# watchdog.net
KiCad netlist of a schematic drawn in Altium Designer
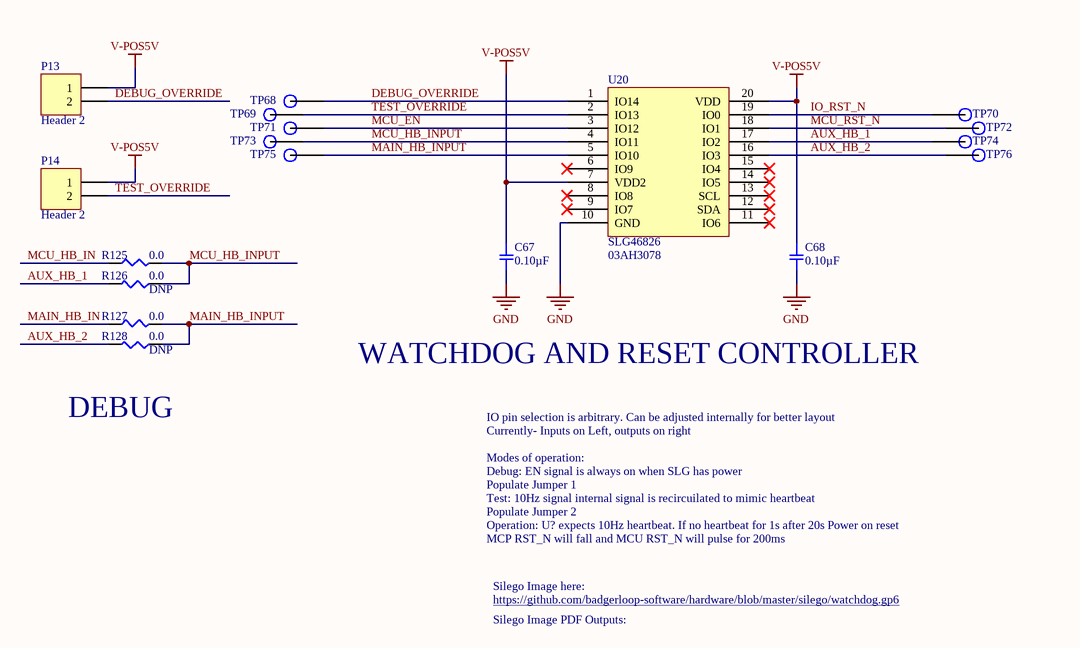
[diagram p0: watchdog.SchDoc]

(export (version "E")
  (design (tool "Eeschema 10.0.6"))
  (components
    (comp (ref "C67")
      (value "0.10µF")
      (footprint "SMD-0805C")
      (description "CAP CER 0.1UF 25V X7R 0805")
      (fields
        (field (name "DIGI-KEY PART NUMBER") "490-12754-1-ND")
        (field (name "PART NUMBER") "GRM219R71E104KA01D")
      )
      (libsource (lib "capacitors") (part "GRM219R71E104KA01D"))
    )
    (comp (ref "C68")
      (value "0.10µF")
      (footprint "SMD-0805C")
      (description "CAP CER 0.1UF 25V X7R 0805")
      (fields
        (field (name "DIGI-KEY PART NUMBER") "490-12754-1-ND")
        (field (name "PART NUMBER") "GRM219R71E104KA01D")
      )
      (libsource (lib "capacitors") (part "GRM219R71E104KA01D"))
    )
    (comp (ref "P13")
      (value "Header 2")
      (footprint "Pin Header 1x2 TH Pitch 2.54mm")
      (description "Header, 2-Pin")
      (fields (field (name "PUBLISHER") "Altium Limited"))
      (libsource (lib "connector") (part "Header 2"))
    )
    (comp (ref "P14")
      (value "Header 2")
      (footprint "Pin Header 1x2 TH Pitch 2.54mm")
      (description "Header, 2-Pin")
      (fields (field (name "PUBLISHER") "Altium Limited"))
      (libsource (lib "connector") (part "Header 2"))
    )
    (comp (ref "R125")
      (value "0.0")
      (footprint "SMD-0805-RES")
      (description "RES SMD 0.0 OHM JUMPER 1/8W 0805")
      (fields (field (name "PART NUMBER") "ERJ-6GEY0R00V") (field (name "DIGI-KEY PART NUMBER") "P0.0ACT-ND"))
      (libsource (lib "resistors") (part "ERJ-6GEY0R00V"))
    )
    (comp (ref "R126")
      (value "0.0")
      (footprint "SMD-0805-RES")
      (description "RES SMD 0.0 OHM JUMPER 1/8W 0805")
      (fields
        (field (name "PART NUMBER") "ERJ-6GEY0R00V")
        (field (name "DIGI-KEY PART NUMBER") "P0.0ACT-ND")
        (field (name "DNP") "DNP")
      )
      (libsource (lib "resistors") (part "ERJ-6GEY0R00V"))
    )
    (comp (ref "R127")
      (value "0.0")
      (footprint "SMD-0805-RES")
      (description "RES SMD 0.0 OHM JUMPER 1/8W 0805")
      (fields (field (name "PART NUMBER") "ERJ-6GEY0R00V") (field (name "DIGI-KEY PART NUMBER") "P0.0ACT-ND"))
      (libsource (lib "resistors") (part "ERJ-6GEY0R00V"))
    )
    (comp (ref "R128")
      (value "0.0")
      (footprint "SMD-0805-RES")
      (description "RES SMD 0.0 OHM JUMPER 1/8W 0805")
      (fields
        (field (name "PART NUMBER") "ERJ-6GEY0R00V")
        (field (name "DIGI-KEY PART NUMBER") "P0.0ACT-ND")
        (field (name "DNP") "DNP")
      )
      (libsource (lib "resistors") (part "ERJ-6GEY0R00V"))
    )
    (comp (ref "TP68")
      (value "TP")
      (footprint "Test Point")
      (description "SMD TEST POINT")
      (libsource (lib "misc") (part "TP"))
    )
    (comp (ref "TP69")
      (value "TP")
      (footprint "Test Point")
      (description "SMD TEST POINT")
      (libsource (lib "misc") (part "TP"))
    )
    (comp (ref "TP70")
      (value "TP")
      (footprint "Test Point")
      (description "SMD TEST POINT")
      (libsource (lib "misc") (part "TP"))
    )
    (comp (ref "TP71")
      (value "TP")
      (footprint "Test Point")
      (description "SMD TEST POINT")
      (libsource (lib "misc") (part "TP"))
    )
    (comp (ref "TP72")
      (value "TP")
      (footprint "Test Point")
      (description "SMD TEST POINT")
      (libsource (lib "misc") (part "TP"))
    )
    (comp (ref "TP73")
      (value "TP")
      (footprint "Test Point")
      (description "SMD TEST POINT")
      (libsource (lib "misc") (part "TP"))
    )
    (comp (ref "TP74")
      (value "TP")
      (footprint "Test Point")
      (description "SMD TEST POINT")
      (libsource (lib "misc") (part "TP"))
    )
    (comp (ref "TP75")
      (value "TP")
      (footprint "Test Point")
      (description "SMD TEST POINT")
      (libsource (lib "misc") (part "TP"))
    )
    (comp (ref "TP76")
      (value "TP")
      (footprint "Test Point")
      (description "SMD TEST POINT")
      (libsource (lib "misc") (part "TP"))
    )
    (comp (ref "U20")
      (value "SLG46826")
      (footprint "SOP65P640X175-20N")
      (description "GreenPAK Programmable Mixed Signal Matrix with In-System Programmability")
      (fields
        (field (name "MANUFACTURER") "Dialog Semiconductor")
        (field (name "MANUFACTURER PART NUMBER") "SLG46826V-SKT")
        (field (name "SUPPLIER PART NUMBER 1") "03AH3078")
      )
      (libsource (lib "ic") (part "SLG46826"))
    )
  )
  (nets
    (net (code "1") (name "/AUX_HB_1") (class "Default")
      (node (ref "R126") (pin "2") (pinfunction "2_2") (pintype "passive"))
      (node (ref "TP74") (pin "1") (pinfunction "1_1") (pintype "passive"))
      (node (ref "U20") (pin "17") (pinfunction "IO2_17") (pintype "passive"))
    )
    (net (code "2") (name "/AUX_HB_2") (class "Default")
      (node (ref "R128") (pin "2") (pinfunction "2_2") (pintype "passive"))
      (node (ref "TP76") (pin "1") (pinfunction "1_1") (pintype "passive"))
      (node (ref "U20") (pin "16") (pinfunction "IO3_16") (pintype "passive"))
    )
    (net (code "3") (name "/DEBUG_OVERRIDE") (class "Default")
      (node (ref "P13") (pin "2") (pinfunction "2_2") (pintype "passive"))
      (node (ref "TP68") (pin "1") (pinfunction "1_1") (pintype "passive"))
      (node (ref "U20") (pin "1") (pinfunction "IO14_1") (pintype "passive"))
    )
    (net (code "4") (name "/IO_RST_N") (class "Default")
      (node (ref "TP70") (pin "1") (pinfunction "1_1") (pintype "passive"))
      (node (ref "U20") (pin "19") (pinfunction "IO0_19") (pintype "passive"))
    )
    (net (code "5") (name "/MAIN_HB_IN") (class "Default")
      (node (ref "R127") (pin "1") (pinfunction "1_1") (pintype "passive"))
    )
    (net (code "6") (name "/MAIN_HB_INPUT") (class "Default")
      (node (ref "R127") (pin "2") (pinfunction "2_2") (pintype "passive"))
      (node (ref "R128") (pin "1") (pinfunction "1_1") (pintype "passive"))
      (node (ref "TP75") (pin "1") (pinfunction "1_1") (pintype "passive"))
      (node (ref "U20") (pin "5") (pinfunction "IO10_5") (pintype "passive"))
    )
    (net (code "7") (name "/MCU_EN") (class "Default")
      (node (ref "TP71") (pin "1") (pinfunction "1_1") (pintype "passive"))
      (node (ref "U20") (pin "3") (pinfunction "IO12_3") (pintype "passive"))
    )
    (net (code "8") (name "/MCU_HB_IN") (class "Default")
      (node (ref "R125") (pin "1") (pinfunction "1_1") (pintype "passive"))
    )
    (net (code "9") (name "/MCU_HB_INPUT") (class "Default")
      (node (ref "R125") (pin "2") (pinfunction "2_2") (pintype "passive"))
      (node (ref "R126") (pin "1") (pinfunction "1_1") (pintype "passive"))
      (node (ref "TP73") (pin "1") (pinfunction "1_1") (pintype "passive"))
      (node (ref "U20") (pin "4") (pinfunction "IO11_4") (pintype "passive"))
    )
    (net (code "10") (name "/MCU_RST_N") (class "Default")
      (node (ref "TP72") (pin "1") (pinfunction "1_1") (pintype "passive"))
      (node (ref "U20") (pin "18") (pinfunction "IO1_18") (pintype "passive"))
    )
    (net (code "11") (name "/TEST_OVERRIDE") (class "Default")
      (node (ref "P14") (pin "2") (pinfunction "2_2") (pintype "passive"))
      (node (ref "TP69") (pin "1") (pinfunction "1_1") (pintype "passive"))
      (node (ref "U20") (pin "2") (pinfunction "IO13_2") (pintype "passive"))
    )
    (net (code "12") (name "GND") (class "Default")
      (node (ref "C67") (pin "2") (pinfunction "2_2") (pintype "passive"))
      (node (ref "C68") (pin "2") (pinfunction "2_2") (pintype "passive"))
      (node (ref "U20") (pin "10") (pinfunction "GND_10") (pintype "passive"))
    )
    (net (code "13") (name "V-POS5V") (class "Default")
      (node (ref "C67") (pin "1") (pinfunction "1_1") (pintype "passive"))
      (node (ref "C68") (pin "1") (pinfunction "1_1") (pintype "passive"))
      (node (ref "P13") (pin "1") (pinfunction "1_1") (pintype "passive"))
      (node (ref "P14") (pin "1") (pinfunction "1_1") (pintype "passive"))
      (node (ref "U20") (pin "20") (pinfunction "VDD_20") (pintype "passive"))
      (node (ref "U20") (pin "7") (pinfunction "VDD2_7") (pintype "passive"))
    )
    (net (code "14") (name "unconnected-(U20-IO4-Pad15)") (class "Default")
      (node (ref "U20") (pin "15") (pinfunction "IO4_15") (pintype "passive+no_connect"))
    )
    (net (code "15") (name "unconnected-(U20-IO5-Pad14)") (class "Default")
      (node (ref "U20") (pin "14") (pinfunction "IO5_14") (pintype "passive+no_connect"))
    )
    (net (code "16") (name "unconnected-(U20-IO6-Pad11)") (class "Default")
      (node (ref "U20") (pin "11") (pinfunction "IO6_11") (pintype "passive+no_connect"))
    )
    (net (code "17") (name "unconnected-(U20-IO7-Pad9)") (class "Default")
      (node (ref "U20") (pin "9") (pinfunction "IO7_9") (pintype "passive+no_connect"))
    )
    (net (code "18") (name "unconnected-(U20-IO8-Pad8)") (class "Default")
      (node (ref "U20") (pin "8") (pinfunction "IO8_8") (pintype "passive+no_connect"))
    )
    (net (code "19") (name "unconnected-(U20-IO9-Pad6)") (class "Default")
      (node (ref "U20") (pin "6") (pinfunction "IO9_6") (pintype "passive+no_connect"))
    )
    (net (code "20") (name "unconnected-(U20-SCL-Pad13)") (class "Default")
      (node (ref "U20") (pin "13") (pinfunction "SCL_13") (pintype "passive+no_connect"))
    )
    (net (code "21") (name "unconnected-(U20-SDA-Pad12)") (class "Default")
      (node (ref "U20") (pin "12") (pinfunction "SDA_12") (pintype "passive+no_connect"))
    )
  )
)
